# PrechargeV3.net
KiCad netlist of a schematic drawn in EAGLE
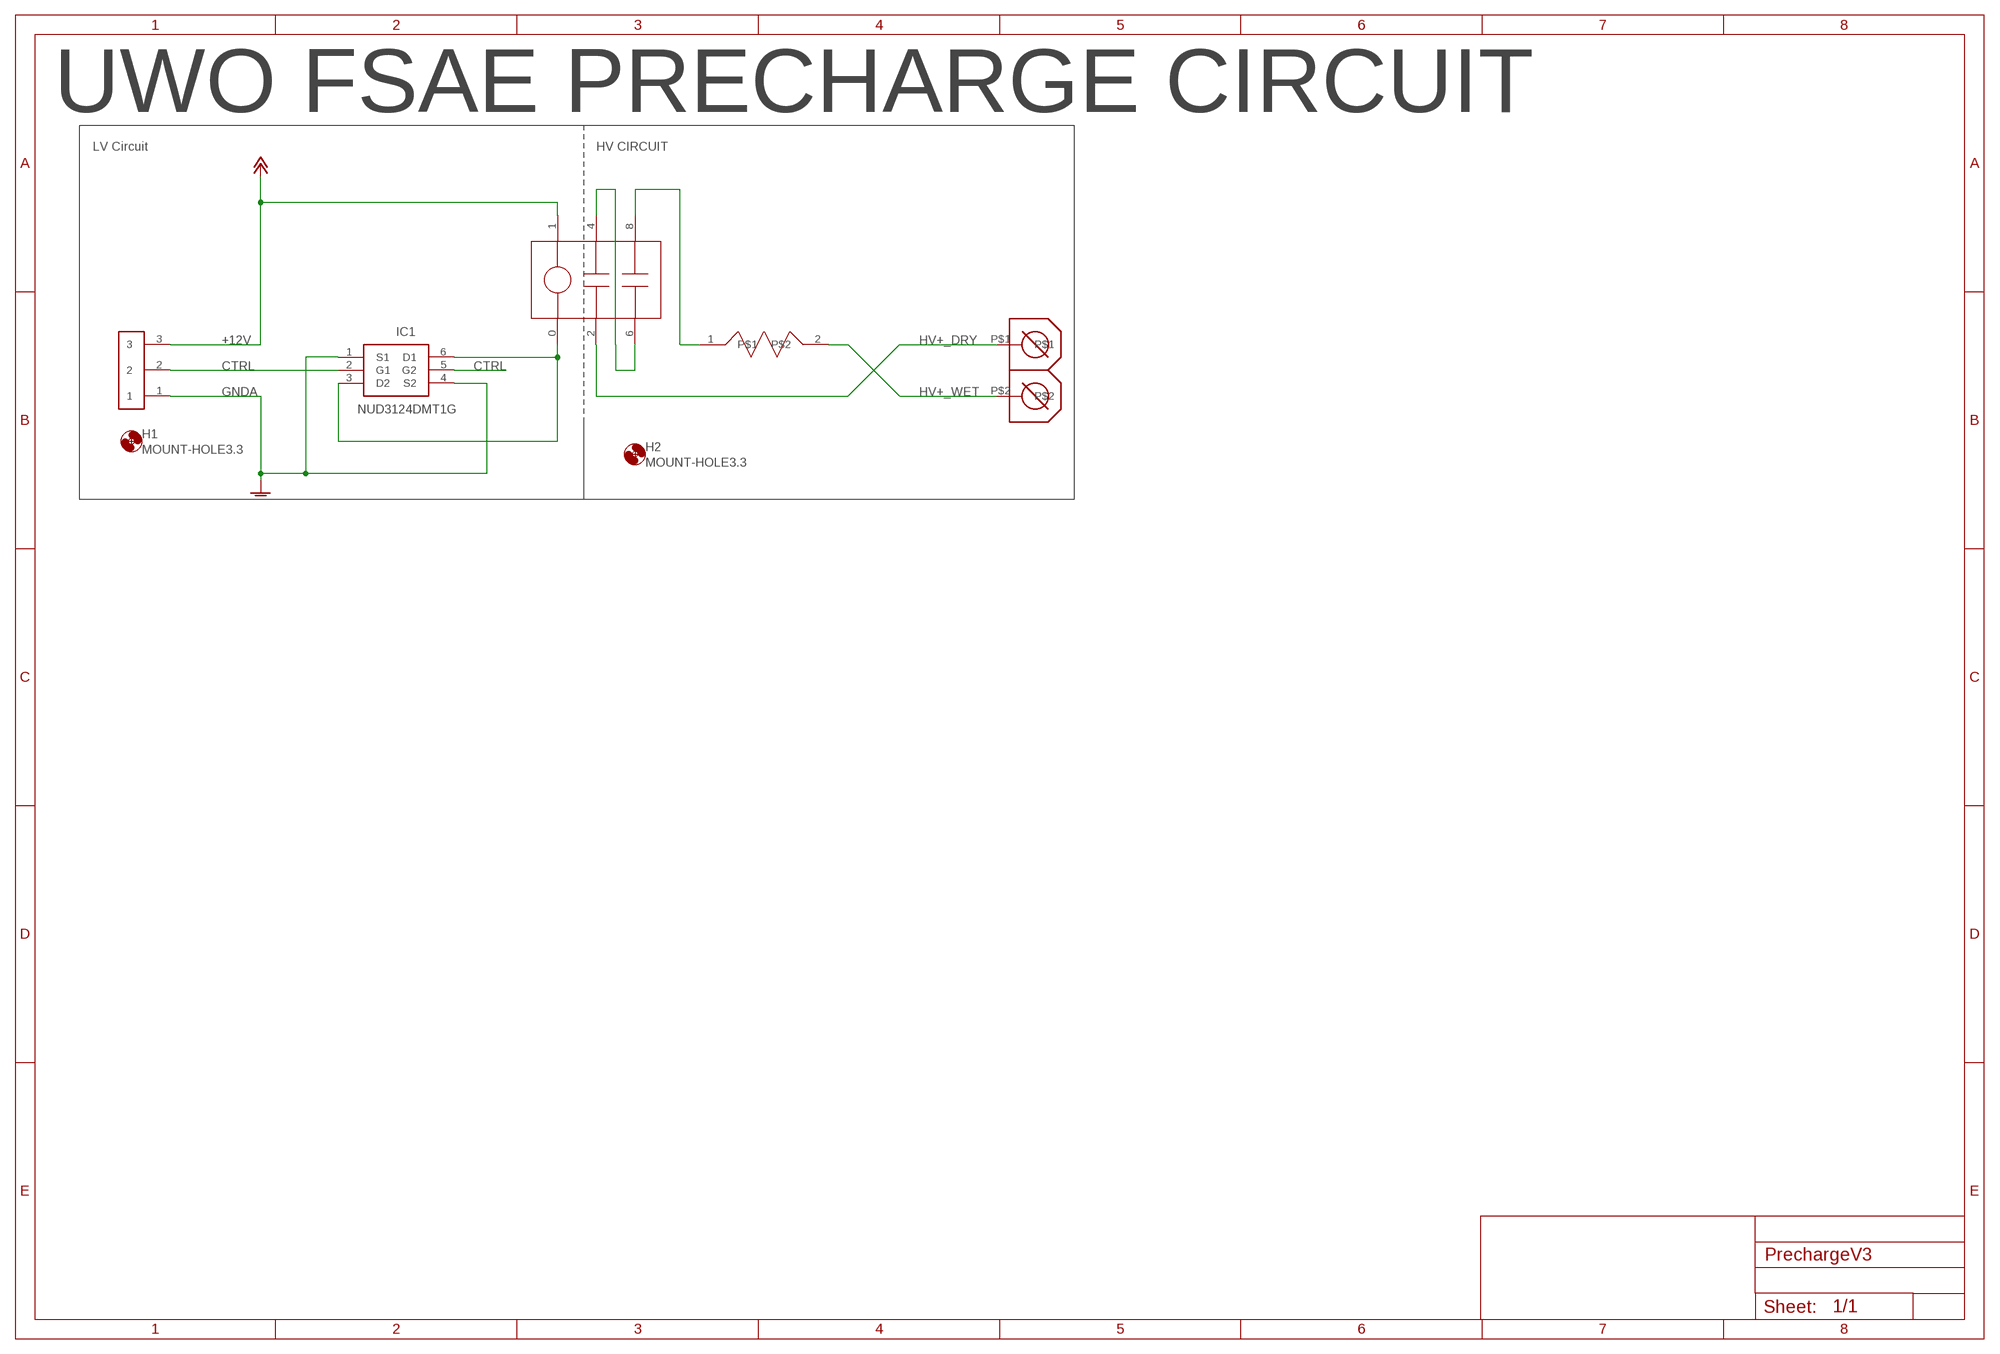
[diagram p0: schematic, sheet 1]

(export (version "E")
  (design (tool "Eeschema 10.0.6"))
  (components
    (comp (ref "H1")
      (value "MOUNT-HOLE3.3")
      (footprint "eagle-import:3,3")
      (libsource (lib "eagle-import") (part "MOUNT-HOLE3.3"))
    )
    (comp (ref "H2")
      (value "MOUNT-HOLE3.3")
      (footprint "eagle-import:3,3")
      (libsource (lib "eagle-import") (part "MOUNT-HOLE3.3"))
    )
    (comp (ref "IC1")
      (value "NUD3124DMT1G")
      (footprint "eagle-import:SAMACSYS_PARTS_SOT95P275X110-6N")
      (fields (field (name "MOUSER_PART_NUMBER") "863-NUD3124DMT1G"))
      (libsource (lib "eagle-import") (part "SAMACSYS_PARTS_NUD3124DMT1G"))
    )
    (comp (ref "U$1")
      (value "TO247RESISTORHEATINK")
      (footprint "eagle-import:_CUSTOM_TO-247-2V")
      (libsource (lib "eagle-import") (part "TO247RESISTORHEATINK"))
    )
    (comp (ref "U$2")
      (value "PHOENIX_1935789")
      (footprint "eagle-import:PHOENIX_1935789")
      (libsource (lib "eagle-import") (part "PHOENIX_1935789"))
    )
    (comp (ref "U$3")
      (value "G7L")
      (footprint "eagle-import:G7L")
      (libsource (lib "eagle-import") (part "G7L"))
    )
    (comp (ref "U$17")
      (value "282838-2_TE")
      (footprint "eagle-import:282838-2_FOOT")
      (libsource (lib "eagle-import") (part "282838-2_TE"))
    )
  )
  (nets
    (net (code "1") (name "+12V") (class "Default")
      (node (ref "U$2") (pin "3") (pinfunction "3_3") (pintype "bidirectional"))
      (node (ref "U$3") (pin "1") (pinfunction "1_1") (pintype "bidirectional"))
    )
    (net (code "2") (name "/CTRL") (class "Default")
      (node (ref "IC1") (pin "2") (pinfunction "G1_2") (pintype "bidirectional"))
      (node (ref "IC1") (pin "5") (pinfunction "G2_5") (pintype "bidirectional"))
      (node (ref "U$2") (pin "2") (pinfunction "2_2") (pintype "bidirectional"))
    )
    (net (code "3") (name "/HV+_DRY") (class "Default")
      (node (ref "U$17") (pin "P$1") (pinfunction "P$1_P$1") (pintype "bidirectional"))
      (node (ref "U$3") (pin "2") (pinfunction "2_2") (pintype "bidirectional"))
    )
    (net (code "4") (name "/HV+_WET") (class "Default")
      (node (ref "U$1") (pin "2") (pinfunction "P$2_2") (pintype "bidirectional"))
      (node (ref "U$17") (pin "P$2") (pinfunction "P$2_P$2") (pintype "bidirectional"))
    )
    (net (code "5") (name "GNDA") (class "Default")
      (node (ref "IC1") (pin "1") (pinfunction "S1_1") (pintype "bidirectional"))
      (node (ref "IC1") (pin "4") (pinfunction "S2_4") (pintype "bidirectional"))
      (node (ref "U$2") (pin "1") (pinfunction "1_1") (pintype "bidirectional"))
    )
    (net (code "6") (name "Net-(IC1-D1)") (class "Default")
      (node (ref "IC1") (pin "3") (pinfunction "D2_3") (pintype "bidirectional"))
      (node (ref "IC1") (pin "6") (pinfunction "D1_6") (pintype "bidirectional"))
      (node (ref "U$3") (pin "0") (pinfunction "0_0") (pintype "bidirectional"))
    )
    (net (code "7") (name "Net-(U$1-P$1)") (class "Default")
      (node (ref "U$1") (pin "1") (pinfunction "P$1_1") (pintype "bidirectional"))
      (node (ref "U$3") (pin "8") (pinfunction "8_8") (pintype "bidirectional"))
    )
    (net (code "8") (name "Net-(U$3-Pad4)") (class "Default")
      (node (ref "U$3") (pin "4") (pinfunction "4_4") (pintype "bidirectional"))
      (node (ref "U$3") (pin "6") (pinfunction "6_6") (pintype "bidirectional"))
    )
  )
)
